# Bridge_Pair_3.net
KiCad netlist of a schematic drawn in Altium Designer
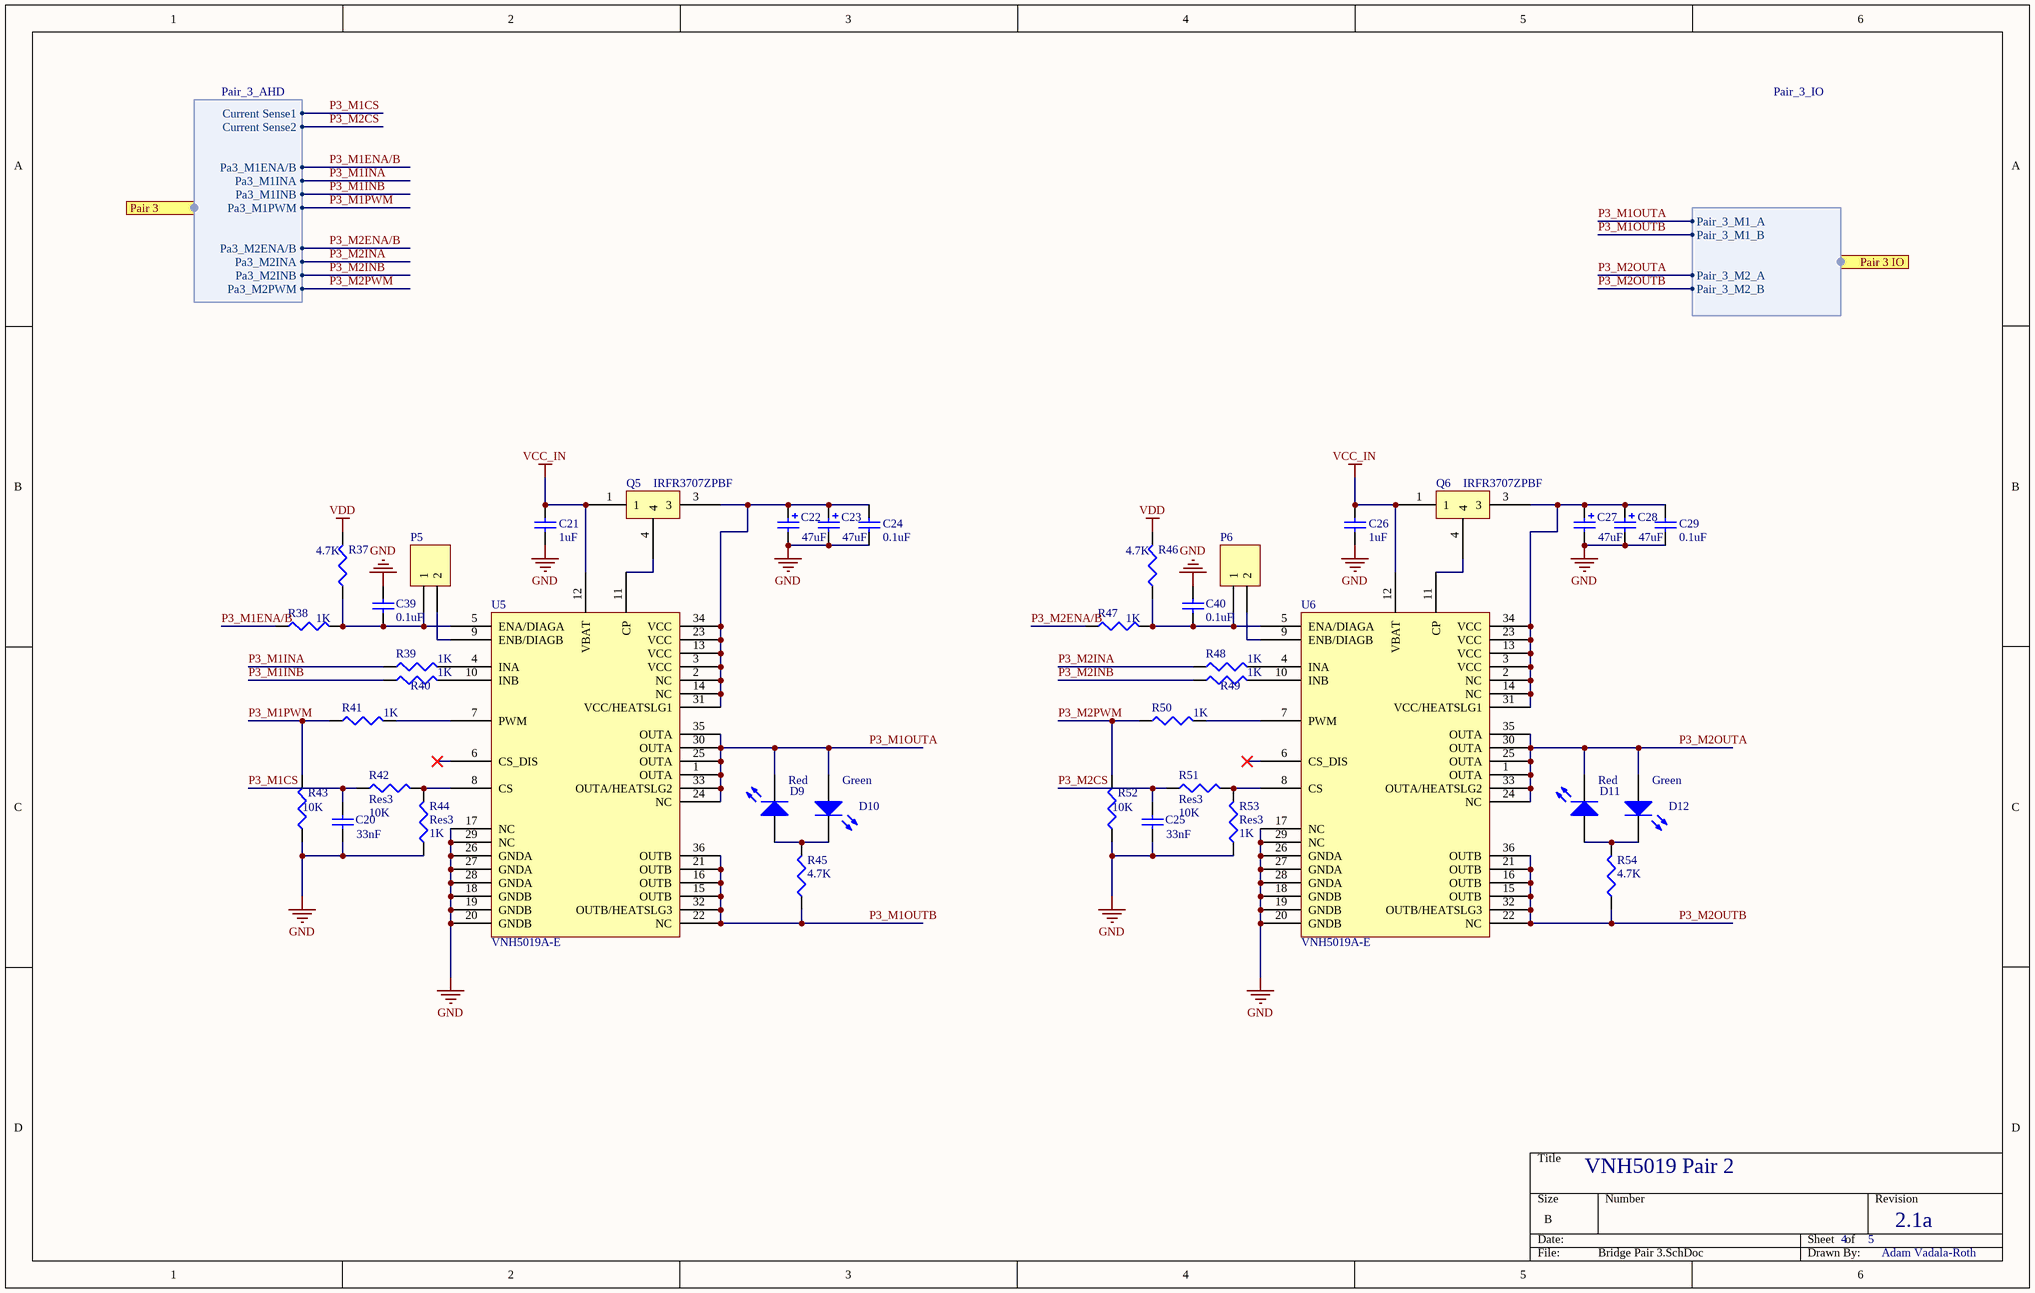
[diagram p0: Bridge Pair 3.SchDoc]

(export (version "E")
  (design (tool "Eeschema 10.0.6"))
  (components
    (comp (ref "C20")
      (value "33nF")
      (footprint "1608[0603]")
      (description "Capacitor (Semiconductor SIM Model)")
      (fields (field (name "Comment") "Cap Semi") (field (name "PUBLISHER") "Altium Limited"))
      (libsource (lib "Miscellaneous Devices") (part "Cap Semi"))
    )
    (comp (ref "C21")
      (value "1uF")
      (footprint "1608[0603]")
      (description "Capacitor (Semiconductor SIM Model)")
      (fields (field (name "Comment") "Cap Semi") (field (name "PUBLISHER") "Altium Limited"))
      (libsource (lib "Miscellaneous Devices") (part "Cap Semi"))
    )
    (comp (ref "C22")
      (value "47uF")
      (footprint "CAPPR2-5x6.8")
      (description "Polarized Capacitor (Axial)")
      (fields (field (name "Comment") "Cap Pol2") (field (name "PUBLISHER") "Altium Limited"))
      (libsource (lib "Miscellaneous Devices") (part "Cap Pol2"))
    )
    (comp (ref "C23")
      (value "47uF")
      (footprint "CAPPR2-5x6.8")
      (description "Polarized Capacitor (Axial)")
      (fields (field (name "Comment") "Cap Pol2") (field (name "PUBLISHER") "Altium Limited"))
      (libsource (lib "Miscellaneous Devices") (part "Cap Pol2"))
    )
    (comp (ref "C24")
      (value "0.1uF")
      (footprint "C1206")
      (description "Capacitor (Semiconductor SIM Model)")
      (fields (field (name "Comment") "Cap Semi") (field (name "PUBLISHER") "Altium Limited"))
      (libsource (lib "Miscellaneous Devices") (part "Cap Semi"))
    )
    (comp (ref "C25")
      (value "33nF")
      (footprint "1608[0603]")
      (description "Capacitor (Semiconductor SIM Model)")
      (fields (field (name "Comment") "Cap Semi") (field (name "PUBLISHER") "Altium Limited"))
      (libsource (lib "Miscellaneous Devices") (part "Cap Semi"))
    )
    (comp (ref "C26")
      (value "1uF")
      (footprint "1608[0603]")
      (description "Capacitor (Semiconductor SIM Model)")
      (fields (field (name "Comment") "Cap Semi") (field (name "PUBLISHER") "Altium Limited"))
      (libsource (lib "Miscellaneous Devices") (part "Cap Semi"))
    )
    (comp (ref "C27")
      (value "47uF")
      (footprint "CAPPR2-5x6.8")
      (description "Polarized Capacitor (Axial)")
      (fields (field (name "Comment") "Cap Pol2") (field (name "PUBLISHER") "Altium Limited"))
      (libsource (lib "Miscellaneous Devices") (part "Cap Pol2"))
    )
    (comp (ref "C28")
      (value "47uF")
      (footprint "CAPPR2-5x6.8")
      (description "Polarized Capacitor (Axial)")
      (fields (field (name "Comment") "Cap Pol2") (field (name "PUBLISHER") "Altium Limited"))
      (libsource (lib "Miscellaneous Devices") (part "Cap Pol2"))
    )
    (comp (ref "C29")
      (value "0.1uF")
      (footprint "C1206")
      (description "Capacitor (Semiconductor SIM Model)")
      (fields (field (name "Comment") "Cap Semi") (field (name "PUBLISHER") "Altium Limited"))
      (libsource (lib "Miscellaneous Devices") (part "Cap Semi"))
    )
    (comp (ref "C39")
      (value "0.1uF")
      (footprint "1608[0603]")
      (description "Capacitor (Semiconductor SIM Model)")
      (fields (field (name "Comment") "Cap Semi") (field (name "PUBLISHER") "Altium Limited"))
      (libsource (lib "Miscellaneous Devices") (part "Cap Semi"))
    )
    (comp (ref "C40")
      (value "0.1uF")
      (footprint "1608[0603]")
      (description "Capacitor (Semiconductor SIM Model)")
      (fields (field (name "Comment") "Cap Semi") (field (name "PUBLISHER") "Altium Limited"))
      (libsource (lib "Miscellaneous Devices") (part "Cap Semi"))
    )
    (comp (ref "D9")
      (value "LED2")
      (footprint "3.2X1.6X1.1")
      (description "Typical RED, GREEN, YELLOW, AMBER GaAs LED")
      (fields (field (name "PUBLISHER") "Altium Limited"))
      (libsource (lib "Miscellaneous Devices") (part "LED2"))
    )
    (comp (ref "D10")
      (value "LED2")
      (footprint "3.2X1.6X1.1")
      (description "Typical RED, GREEN, YELLOW, AMBER GaAs LED")
      (fields (field (name "PUBLISHER") "Altium Limited"))
      (libsource (lib "Miscellaneous Devices") (part "LED2"))
    )
    (comp (ref "D11")
      (value "LED2")
      (footprint "3.2X1.6X1.1")
      (description "Typical RED, GREEN, YELLOW, AMBER GaAs LED")
      (fields (field (name "PUBLISHER") "Altium Limited"))
      (libsource (lib "Miscellaneous Devices") (part "LED2"))
    )
    (comp (ref "D12")
      (value "LED2")
      (footprint "3.2X1.6X1.1")
      (description "Typical RED, GREEN, YELLOW, AMBER GaAs LED")
      (fields (field (name "PUBLISHER") "Altium Limited"))
      (libsource (lib "Miscellaneous Devices") (part "LED2"))
    )
    (comp (ref "P5")
      (value "Header 2")
      (footprint "HDR1X2")
      (description "Header, 2-Pin")
      (fields (field (name "PUBLISHER") "Altium Limited"))
      (libsource (lib "Miscellaneous Connectors") (part "Header 2"))
    )
    (comp (ref "P6")
      (value "Header 2")
      (footprint "HDR1X2")
      (description "Header, 2-Pin")
      (fields (field (name "PUBLISHER") "Altium Limited"))
      (libsource (lib "Miscellaneous Connectors") (part "Header 2"))
    )
    (comp (ref "Q5")
      (value "IRFR3707ZPBF")
      (footprint "IRFR3707ZPBF")
      (description "Power FET")
      (libsource (lib "Thruster Shield Part Library") (part "IRFR3707ZPBF"))
    )
    (comp (ref "Q6")
      (value "IRFR3707ZPBF")
      (footprint "IRFR3707ZPBF")
      (description "Power FET")
      (libsource (lib "Thruster Shield Part Library") (part "IRFR3707ZPBF"))
    )
    (comp (ref "R37")
      (value "4.7K")
      (footprint "RESC1608L")
      (description "Resistor")
      (fields (field (name "Comment") "Res3") (field (name "PUBLISHER") "Altium Limited"))
      (libsource (lib "Miscellaneous Devices") (part "Res3"))
    )
    (comp (ref "R38")
      (value "1K")
      (footprint "RESC1608L")
      (description "Resistor")
      (fields (field (name "Comment") "Res3") (field (name "PUBLISHER") "Altium Limited"))
      (libsource (lib "Miscellaneous Devices") (part "Res3"))
    )
    (comp (ref "R39")
      (value "1K")
      (footprint "RESC1608L")
      (description "Resistor")
      (fields (field (name "Comment") "Res3") (field (name "PUBLISHER") "Altium Limited"))
      (libsource (lib "Miscellaneous Devices") (part "Res3"))
    )
    (comp (ref "R40")
      (value "1K")
      (footprint "RESC1608L")
      (description "Resistor")
      (fields (field (name "Comment") "Res3") (field (name "PUBLISHER") "Altium Limited"))
      (libsource (lib "Miscellaneous Devices") (part "Res3"))
    )
    (comp (ref "R41")
      (value "1K")
      (footprint "RESC1608L")
      (description "Resistor")
      (fields (field (name "Comment") "Res3") (field (name "PUBLISHER") "Altium Limited"))
      (libsource (lib "Miscellaneous Devices") (part "Res3"))
    )
    (comp (ref "R42")
      (value "Res3")
      (footprint "RESC1608L")
      (description "Resistor")
      (fields (field (name "ALTIUM_VALUE") "10K") (field (name "PUBLISHER") "Altium Limited"))
      (libsource (lib "Miscellaneous Devices") (part "Res3"))
    )
    (comp (ref "R43")
      (value "10K")
      (footprint "RESC1608L")
      (description "Resistor")
      (fields (field (name "Comment") "Res3") (field (name "PUBLISHER") "Altium Limited"))
      (libsource (lib "Miscellaneous Devices") (part "Res3"))
    )
    (comp (ref "R44")
      (value "Res3")
      (footprint "RESC1608L")
      (description "Resistor")
      (fields (field (name "ALTIUM_VALUE") "1K") (field (name "PUBLISHER") "Altium Limited"))
      (libsource (lib "Miscellaneous Devices") (part "Res3"))
    )
    (comp (ref "R45")
      (value "4.7K")
      (footprint "0805 SMD Resistor")
      (description "Resistor")
      (fields (field (name "Comment") "Res3") (field (name "PUBLISHER") "Altium Limited"))
      (libsource (lib "Miscellaneous Devices") (part "Res3"))
    )
    (comp (ref "R46")
      (value "4.7K")
      (footprint "RESC1608L")
      (description "Resistor")
      (fields (field (name "Comment") "Res3") (field (name "PUBLISHER") "Altium Limited"))
      (libsource (lib "Miscellaneous Devices") (part "Res3"))
    )
    (comp (ref "R47")
      (value "1K")
      (footprint "RESC1608L")
      (description "Resistor")
      (fields (field (name "Comment") "Res3") (field (name "PUBLISHER") "Altium Limited"))
      (libsource (lib "Miscellaneous Devices") (part "Res3"))
    )
    (comp (ref "R48")
      (value "1K")
      (footprint "RESC1608L")
      (description "Resistor")
      (fields (field (name "Comment") "Res3") (field (name "PUBLISHER") "Altium Limited"))
      (libsource (lib "Miscellaneous Devices") (part "Res3"))
    )
    (comp (ref "R49")
      (value "1K")
      (footprint "RESC1608L")
      (description "Resistor")
      (fields (field (name "Comment") "Res3") (field (name "PUBLISHER") "Altium Limited"))
      (libsource (lib "Miscellaneous Devices") (part "Res3"))
    )
    (comp (ref "R50")
      (value "1K")
      (footprint "RESC1608L")
      (description "Resistor")
      (fields (field (name "Comment") "Res3") (field (name "PUBLISHER") "Altium Limited"))
      (libsource (lib "Miscellaneous Devices") (part "Res3"))
    )
    (comp (ref "R51")
      (value "Res3")
      (footprint "RESC1608L")
      (description "Resistor")
      (fields (field (name "ALTIUM_VALUE") "10K") (field (name "PUBLISHER") "Altium Limited"))
      (libsource (lib "Miscellaneous Devices") (part "Res3"))
    )
    (comp (ref "R52")
      (value "10K")
      (footprint "RESC1608L")
      (description "Resistor")
      (fields (field (name "Comment") "Res3") (field (name "PUBLISHER") "Altium Limited"))
      (libsource (lib "Miscellaneous Devices") (part "Res3"))
    )
    (comp (ref "R53")
      (value "Res3")
      (footprint "RESC1608L")
      (description "Resistor")
      (fields (field (name "ALTIUM_VALUE") "1K") (field (name "PUBLISHER") "Altium Limited"))
      (libsource (lib "Miscellaneous Devices") (part "Res3"))
    )
    (comp (ref "R54")
      (value "4.7K")
      (footprint "0805 SMD Resistor")
      (description "Resistor")
      (fields (field (name "Comment") "Res3") (field (name "PUBLISHER") "Altium Limited"))
      (libsource (lib "Miscellaneous Devices") (part "Res3"))
    )
    (comp (ref "U5")
      (value "VNH5019A-E")
      (footprint "VNH5019A-E")
      (description "VNH5019A-E H-Bridge")
      (libsource (lib "Ballast and Depth Controller Library") (part "VNH5019A-E"))
    )
    (comp (ref "U6")
      (value "VNH5019A-E")
      (footprint "VNH5019A-E")
      (description "VNH5019A-E H-Bridge")
      (libsource (lib "Ballast and Depth Controller Library") (part "VNH5019A-E"))
    )
  )
  (nets
    (net (code "3") (name "/P3_M1CS") (class "Default")
      (node (ref "C20") (pin "2") (pinfunction "2_2") (pintype "passive"))
      (node (ref "R42") (pin "1") (pinfunction "1_1") (pintype "passive"))
    )
    (net (code "4") (name "/P3_M1ENA{slash}B") (class "Default")
      (node (ref "R38") (pin "1") (pinfunction "1_1") (pintype "passive"))
    )
    (net (code "5") (name "/P3_M1INA") (class "Default")
      (node (ref "R39") (pin "1") (pinfunction "1_1") (pintype "passive"))
    )
    (net (code "6") (name "/P3_M1INB") (class "Default")
      (node (ref "R40") (pin "1") (pinfunction "1_1") (pintype "passive"))
    )
    (net (code "7") (name "/P3_M1OUTA") (class "Default")
      (node (ref "D10") (pin "1") (pinfunction "A_1") (pintype "passive"))
      (node (ref "D9") (pin "2") (pinfunction "K_2") (pintype "passive"))
      (node (ref "U5") (pin "1") (pinfunction "OUTA_1") (pintype "passive"))
      (node (ref "U5") (pin "24") (pinfunction "NC_24") (pintype "passive"))
      (node (ref "U5") (pin "25") (pinfunction "OUTA_25") (pintype "passive"))
      (node (ref "U5") (pin "30") (pinfunction "OUTA_30") (pintype "passive"))
      (node (ref "U5") (pin "33") (pinfunction "OUTA/HEATSLG2_33") (pintype "passive"))
      (node (ref "U5") (pin "35") (pinfunction "OUTA_35") (pintype "passive"))
    )
    (net (code "8") (name "/P3_M1OUTB") (class "Default")
      (node (ref "R45") (pin "1") (pinfunction "1_1") (pintype "passive"))
      (node (ref "U5") (pin "15") (pinfunction "OUTB_15") (pintype "passive"))
      (node (ref "U5") (pin "16") (pinfunction "OUTB_16") (pintype "passive"))
      (node (ref "U5") (pin "21") (pinfunction "OUTB_21") (pintype "passive"))
      (node (ref "U5") (pin "22") (pinfunction "NC_22") (pintype "passive"))
      (node (ref "U5") (pin "32") (pinfunction "OUTB/HEATSLG3_32") (pintype "passive"))
      (node (ref "U5") (pin "36") (pinfunction "OUTB_36") (pintype "passive"))
    )
    (net (code "9") (name "/P3_M1PWM") (class "Default")
      (node (ref "R41") (pin "1") (pinfunction "1_1") (pintype "passive"))
      (node (ref "R43") (pin "2") (pinfunction "2_2") (pintype "passive"))
    )
    (net (code "10") (name "/P3_M2CS") (class "Default")
      (node (ref "C25") (pin "2") (pinfunction "2_2") (pintype "passive"))
      (node (ref "R51") (pin "1") (pinfunction "1_1") (pintype "passive"))
    )
    (net (code "11") (name "/P3_M2ENA{slash}B") (class "Default")
      (node (ref "R47") (pin "1") (pinfunction "1_1") (pintype "passive"))
    )
    (net (code "12") (name "/P3_M2INA") (class "Default")
      (node (ref "R48") (pin "1") (pinfunction "1_1") (pintype "passive"))
    )
    (net (code "13") (name "/P3_M2INB") (class "Default")
      (node (ref "R49") (pin "1") (pinfunction "1_1") (pintype "passive"))
    )
    (net (code "14") (name "/P3_M2OUTA") (class "Default")
      (node (ref "D11") (pin "2") (pinfunction "K_2") (pintype "passive"))
      (node (ref "D12") (pin "1") (pinfunction "A_1") (pintype "passive"))
      (node (ref "U6") (pin "1") (pinfunction "OUTA_1") (pintype "passive"))
      (node (ref "U6") (pin "24") (pinfunction "NC_24") (pintype "passive"))
      (node (ref "U6") (pin "25") (pinfunction "OUTA_25") (pintype "passive"))
      (node (ref "U6") (pin "30") (pinfunction "OUTA_30") (pintype "passive"))
      (node (ref "U6") (pin "33") (pinfunction "OUTA/HEATSLG2_33") (pintype "passive"))
      (node (ref "U6") (pin "35") (pinfunction "OUTA_35") (pintype "passive"))
    )
    (net (code "15") (name "/P3_M2OUTB") (class "Default")
      (node (ref "R54") (pin "1") (pinfunction "1_1") (pintype "passive"))
      (node (ref "U6") (pin "15") (pinfunction "OUTB_15") (pintype "passive"))
      (node (ref "U6") (pin "16") (pinfunction "OUTB_16") (pintype "passive"))
      (node (ref "U6") (pin "21") (pinfunction "OUTB_21") (pintype "passive"))
      (node (ref "U6") (pin "22") (pinfunction "NC_22") (pintype "passive"))
      (node (ref "U6") (pin "32") (pinfunction "OUTB/HEATSLG3_32") (pintype "passive"))
      (node (ref "U6") (pin "36") (pinfunction "OUTB_36") (pintype "passive"))
    )
    (net (code "16") (name "/P3_M2PWM") (class "Default")
      (node (ref "R50") (pin "1") (pinfunction "1_1") (pintype "passive"))
      (node (ref "R52") (pin "2") (pinfunction "2_2") (pintype "passive"))
    )
    (net (code "19") (name "GND") (class "Default")
      (node (ref "C20") (pin "1") (pinfunction "1_1") (pintype "passive"))
      (node (ref "C21") (pin "1") (pinfunction "1_1") (pintype "passive"))
      (node (ref "C22") (pin "2") (pinfunction "2_2") (pintype "passive"))
      (node (ref "C23") (pin "2") (pinfunction "2_2") (pintype "passive"))
      (node (ref "C24") (pin "1") (pinfunction "1_1") (pintype "passive"))
      (node (ref "C25") (pin "1") (pinfunction "1_1") (pintype "passive"))
      (node (ref "C26") (pin "1") (pinfunction "1_1") (pintype "passive"))
      (node (ref "C27") (pin "2") (pinfunction "2_2") (pintype "passive"))
      (node (ref "C28") (pin "2") (pinfunction "2_2") (pintype "passive"))
      (node (ref "C29") (pin "1") (pinfunction "1_1") (pintype "passive"))
      (node (ref "C39") (pin "1") (pinfunction "1_1") (pintype "passive"))
      (node (ref "C40") (pin "1") (pinfunction "1_1") (pintype "passive"))
      (node (ref "R43") (pin "1") (pinfunction "1_1") (pintype "passive"))
      (node (ref "R44") (pin "1") (pinfunction "1_1") (pintype "passive"))
      (node (ref "R52") (pin "1") (pinfunction "1_1") (pintype "passive"))
      (node (ref "R53") (pin "1") (pinfunction "1_1") (pintype "passive"))
      (node (ref "U5") (pin "17") (pinfunction "NC_17") (pintype "passive"))
      (node (ref "U5") (pin "18") (pinfunction "GNDB_18") (pintype "passive"))
      (node (ref "U5") (pin "19") (pinfunction "GNDB_19") (pintype "passive"))
      (node (ref "U5") (pin "20") (pinfunction "GNDB_20") (pintype "passive"))
      (node (ref "U5") (pin "26") (pinfunction "GNDA_26") (pintype "passive"))
      (node (ref "U5") (pin "27") (pinfunction "GNDA_27") (pintype "passive"))
      (node (ref "U5") (pin "28") (pinfunction "GNDA_28") (pintype "passive"))
      (node (ref "U5") (pin "29") (pinfunction "NC_29") (pintype "passive"))
      (node (ref "U6") (pin "17") (pinfunction "NC_17") (pintype "passive"))
      (node (ref "U6") (pin "18") (pinfunction "GNDB_18") (pintype "passive"))
      (node (ref "U6") (pin "19") (pinfunction "GNDB_19") (pintype "passive"))
      (node (ref "U6") (pin "20") (pinfunction "GNDB_20") (pintype "passive"))
      (node (ref "U6") (pin "26") (pinfunction "GNDA_26") (pintype "passive"))
      (node (ref "U6") (pin "27") (pinfunction "GNDA_27") (pintype "passive"))
      (node (ref "U6") (pin "28") (pinfunction "GNDA_28") (pintype "passive"))
      (node (ref "U6") (pin "29") (pinfunction "NC_29") (pintype "passive"))
    )
    (net (code "20") (name "Net-(D10-K)") (class "Default")
      (node (ref "D10") (pin "2") (pinfunction "K_2") (pintype "passive"))
      (node (ref "D9") (pin "1") (pinfunction "A_1") (pintype "passive"))
      (node (ref "R45") (pin "2") (pinfunction "2_2") (pintype "passive"))
    )
    (net (code "21") (name "Net-(D11-A)") (class "Default")
      (node (ref "D11") (pin "1") (pinfunction "A_1") (pintype "passive"))
      (node (ref "D12") (pin "2") (pinfunction "K_2") (pintype "passive"))
      (node (ref "R54") (pin "2") (pinfunction "2_2") (pintype "passive"))
    )
    (net (code "22") (name "Net-(U5-CP)") (class "Default")
      (node (ref "Q5") (pin "4") (pinfunction "4_4") (pintype "passive"))
      (node (ref "U5") (pin "11") (pinfunction "CP_11") (pintype "passive"))
    )
    (net (code "23") (name "Net-(U5-CS)") (class "Default")
      (node (ref "R42") (pin "2") (pinfunction "2_2") (pintype "passive"))
      (node (ref "R44") (pin "2") (pinfunction "2_2") (pintype "passive"))
      (node (ref "U5") (pin "8") (pinfunction "CS_8") (pintype "passive"))
    )
    (net (code "24") (name "Net-(U5-ENA{slash}DIAGA)") (class "Default")
      (node (ref "C39") (pin "2") (pinfunction "2_2") (pintype "passive"))
      (node (ref "P5") (pin "1") (pinfunction "1_1") (pintype "passive"))
      (node (ref "R37") (pin "1") (pinfunction "1_1") (pintype "passive"))
      (node (ref "R38") (pin "2") (pinfunction "2_2") (pintype "passive"))
      (node (ref "U5") (pin "5") (pinfunction "ENA/DIAGA_5") (pintype "passive"))
    )
    (net (code "25") (name "Net-(U5-ENB{slash}DIAGB)") (class "Default")
      (node (ref "P5") (pin "2") (pinfunction "2_2") (pintype "passive"))
      (node (ref "U5") (pin "9") (pinfunction "ENB/DIAGB_9") (pintype "passive"))
    )
    (net (code "26") (name "Net-(U5-INA)") (class "Default")
      (node (ref "R39") (pin "2") (pinfunction "2_2") (pintype "passive"))
      (node (ref "U5") (pin "4") (pinfunction "INA_4") (pintype "passive"))
    )
    (net (code "27") (name "Net-(U5-INB)") (class "Default")
      (node (ref "R40") (pin "2") (pinfunction "2_2") (pintype "passive"))
      (node (ref "U5") (pin "10") (pinfunction "INB_10") (pintype "passive"))
    )
    (net (code "28") (name "Net-(U5-PWM)") (class "Default")
      (node (ref "R41") (pin "2") (pinfunction "2_2") (pintype "passive"))
      (node (ref "U5") (pin "7") (pinfunction "PWM_7") (pintype "passive"))
    )
    (net (code "29") (name "Net-(U5-VCC{slash}HEATSLG1)") (class "Default")
      (node (ref "C22") (pin "1") (pinfunction "1_1") (pintype "passive"))
      (node (ref "C23") (pin "1") (pinfunction "1_1") (pintype "passive"))
      (node (ref "C24") (pin "2") (pinfunction "2_2") (pintype "passive"))
      (node (ref "Q5") (pin "3") (pinfunction "3_3") (pintype "passive"))
      (node (ref "U5") (pin "13") (pinfunction "VCC_13") (pintype "passive"))
      (node (ref "U5") (pin "14") (pinfunction "NC_14") (pintype "passive"))
      (node (ref "U5") (pin "2") (pinfunction "NC_2") (pintype "passive"))
      (node (ref "U5") (pin "23") (pinfunction "VCC_23") (pintype "passive"))
      (node (ref "U5") (pin "3") (pinfunction "VCC_3") (pintype "passive"))
      (node (ref "U5") (pin "31") (pinfunction "VCC/HEATSLG1_31") (pintype "passive"))
      (node (ref "U5") (pin "34") (pinfunction "VCC_34") (pintype "passive"))
    )
    (net (code "30") (name "Net-(U6-CP)") (class "Default")
      (node (ref "Q6") (pin "4") (pinfunction "4_4") (pintype "passive"))
      (node (ref "U6") (pin "11") (pinfunction "CP_11") (pintype "passive"))
    )
    (net (code "31") (name "Net-(U6-CS)") (class "Default")
      (node (ref "R51") (pin "2") (pinfunction "2_2") (pintype "passive"))
      (node (ref "R53") (pin "2") (pinfunction "2_2") (pintype "passive"))
      (node (ref "U6") (pin "8") (pinfunction "CS_8") (pintype "passive"))
    )
    (net (code "32") (name "Net-(U6-ENA{slash}DIAGA)") (class "Default")
      (node (ref "C40") (pin "2") (pinfunction "2_2") (pintype "passive"))
      (node (ref "P6") (pin "1") (pinfunction "1_1") (pintype "passive"))
      (node (ref "R46") (pin "1") (pinfunction "1_1") (pintype "passive"))
      (node (ref "R47") (pin "2") (pinfunction "2_2") (pintype "passive"))
      (node (ref "U6") (pin "5") (pinfunction "ENA/DIAGA_5") (pintype "passive"))
    )
    (net (code "33") (name "Net-(U6-ENB{slash}DIAGB)") (class "Default")
      (node (ref "P6") (pin "2") (pinfunction "2_2") (pintype "passive"))
      (node (ref "U6") (pin "9") (pinfunction "ENB/DIAGB_9") (pintype "passive"))
    )
    (net (code "34") (name "Net-(U6-INA)") (class "Default")
      (node (ref "R48") (pin "2") (pinfunction "2_2") (pintype "passive"))
      (node (ref "U6") (pin "4") (pinfunction "INA_4") (pintype "passive"))
    )
    (net (code "35") (name "Net-(U6-INB)") (class "Default")
      (node (ref "R49") (pin "2") (pinfunction "2_2") (pintype "passive"))
      (node (ref "U6") (pin "10") (pinfunction "INB_10") (pintype "passive"))
    )
    (net (code "36") (name "Net-(U6-PWM)") (class "Default")
      (node (ref "R50") (pin "2") (pinfunction "2_2") (pintype "passive"))
      (node (ref "U6") (pin "7") (pinfunction "PWM_7") (pintype "passive"))
    )
    (net (code "37") (name "Net-(U6-VCC{slash}HEATSLG1)") (class "Default")
      (node (ref "C27") (pin "1") (pinfunction "1_1") (pintype "passive"))
      (node (ref "C28") (pin "1") (pinfunction "1_1") (pintype "passive"))
      (node (ref "C29") (pin "2") (pinfunction "2_2") (pintype "passive"))
      (node (ref "Q6") (pin "3") (pinfunction "3_3") (pintype "passive"))
      (node (ref "U6") (pin "13") (pinfunction "VCC_13") (pintype "passive"))
      (node (ref "U6") (pin "14") (pinfunction "NC_14") (pintype "passive"))
      (node (ref "U6") (pin "2") (pinfunction "NC_2") (pintype "passive"))
      (node (ref "U6") (pin "23") (pinfunction "VCC_23") (pintype "passive"))
      (node (ref "U6") (pin "3") (pinfunction "VCC_3") (pintype "passive"))
      (node (ref "U6") (pin "31") (pinfunction "VCC/HEATSLG1_31") (pintype "passive"))
      (node (ref "U6") (pin "34") (pinfunction "VCC_34") (pintype "passive"))
    )
    (net (code "38") (name "VCC_IN") (class "Default")
      (node (ref "C21") (pin "2") (pinfunction "2_2") (pintype "passive"))
      (node (ref "C26") (pin "2") (pinfunction "2_2") (pintype "passive"))
      (node (ref "Q5") (pin "1") (pinfunction "1_1") (pintype "passive"))
      (node (ref "Q6") (pin "1") (pinfunction "1_1") (pintype "passive"))
      (node (ref "U5") (pin "12") (pinfunction "VBAT_12") (pintype "passive"))
      (node (ref "U6") (pin "12") (pinfunction "VBAT_12") (pintype "passive"))
    )
    (net (code "39") (name "VDD") (class "Default")
      (node (ref "R37") (pin "2") (pinfunction "2_2") (pintype "passive"))
      (node (ref "R46") (pin "2") (pinfunction "2_2") (pintype "passive"))
    )
    (net (code "40") (name "unconnected-(U5-CS_DIS-Pad6)") (class "Default")
      (node (ref "U5") (pin "6") (pinfunction "CS_DIS_6") (pintype "passive+no_connect"))
    )
    (net (code "41") (name "unconnected-(U6-CS_DIS-Pad6)") (class "Default")
      (node (ref "U6") (pin "6") (pinfunction "CS_DIS_6") (pintype "passive+no_connect"))
    )
  )
)
